# MCU.net
KiCad netlist of a schematic drawn in Altium Designer
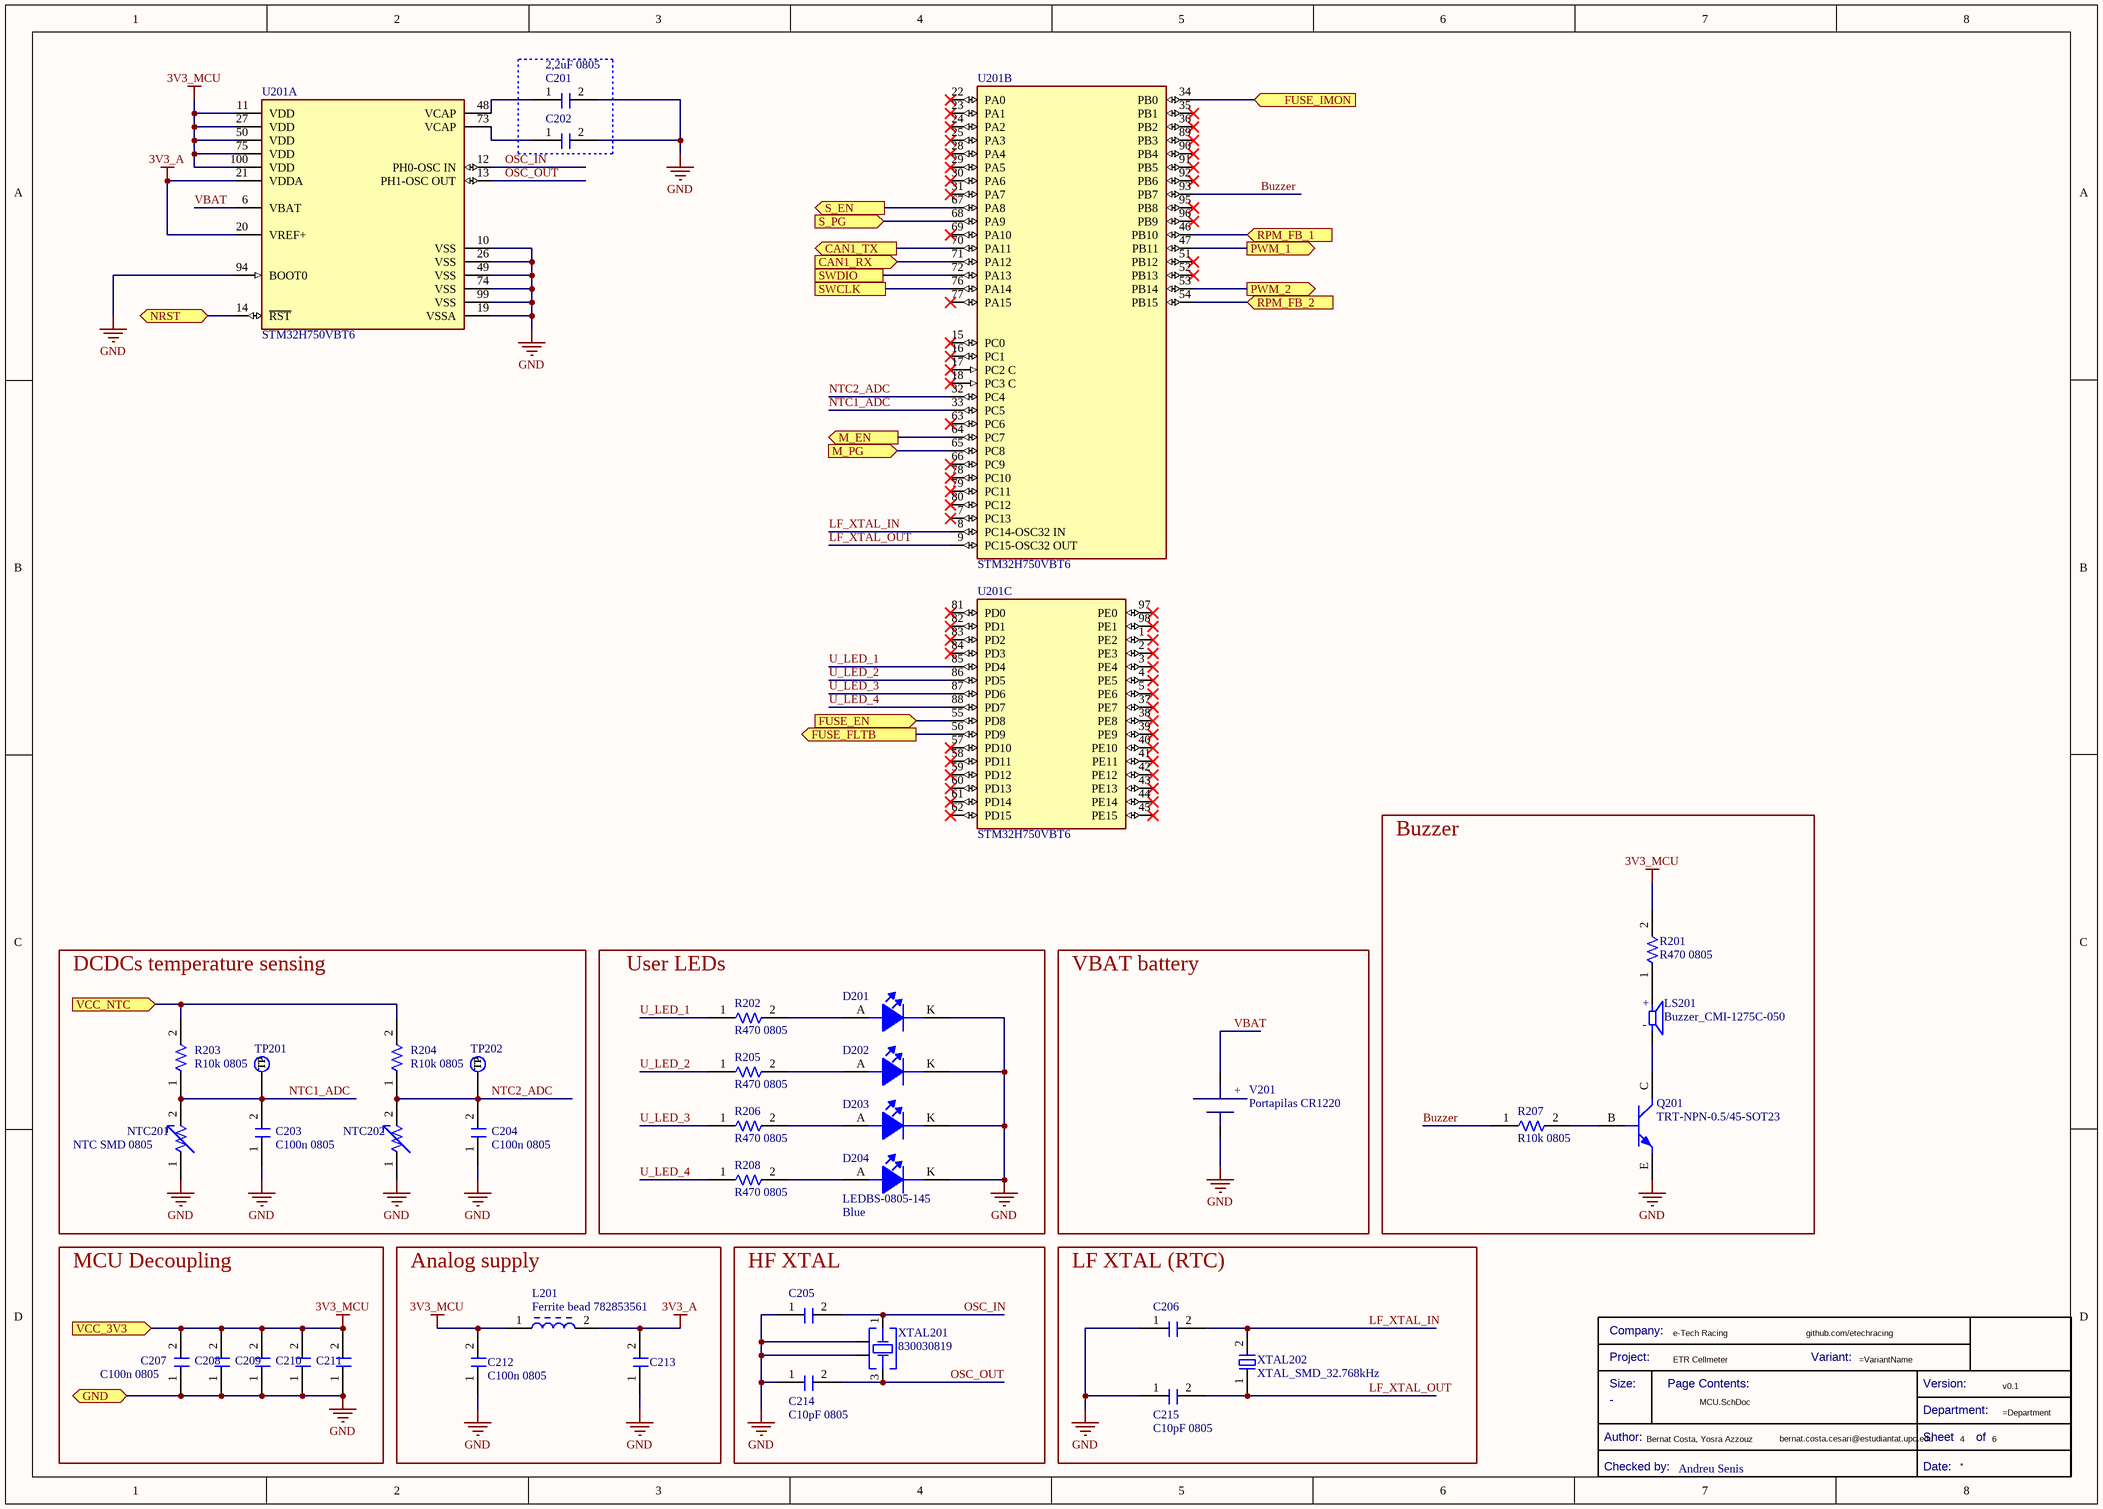
[diagram p0: MCU.SchDoc]

(export (version "E")
  (design (tool "Eeschema 10.0.6"))
  (components
    (comp (ref "C201")
      (value "2,2uF 0805")
      (footprint "C0805FNPC-W")
      (fields
        (field (name "MANUFACTURER") "Wurth Electronics")
        (field (name "TOLERANCE") "20%")
        (field (name "MANUFACTURER PART NUMBER") "885012107011")
        (field (name ".CREATOR") "DR")
      )
      (libsource (lib "EMEA- E-Tech Racing- I'Escola d'Enginyeria de Barcelona Est") (part "C100p-50V-0805FNPC-C0G/NP0"))
    )
    (comp (ref "C202")
      (value "2,2uF 0805")
      (footprint "C0805FNPC-W")
      (fields
        (field (name "MANUFACTURER") "Wurth Electronics")
        (field (name "TOLERANCE") "20%")
        (field (name "MANUFACTURER PART NUMBER") "885012107011")
        (field (name ".CREATOR") "DR")
      )
      (libsource (lib "EMEA- E-Tech Racing- I'Escola d'Enginyeria de Barcelona Est") (part "C100p-50V-0805FNPC-C0G/NP0"))
    )
    (comp (ref "C203")
      (value "C100n 0805")
      (footprint "C0805FNPC-R")
      (description "Cap, 0.1ΜF, 50V, 10%, X7R, 0805")
      (fields (field (name "TOLERANCE") "10%") (field (name ".CREATOR") "DR"))
      (libsource (lib "EMEA- E-Tech Racing- I'Escola d'Enginyeria de Barcelona Est") (part "C100p-50V-0805FNPC-C0G/NP0"))
    )
    (comp (ref "C204")
      (value "C100n 0805")
      (footprint "C0805FNPC-R")
      (description "Cap, 0.1ΜF, 50V, 10%, X7R, 0805")
      (fields (field (name "TOLERANCE") "10%") (field (name ".CREATOR") "DR"))
      (libsource (lib "EMEA- E-Tech Racing- I'Escola d'Enginyeria de Barcelona Est") (part "C100p-50V-0805FNPC-C0G/NP0"))
    )
    (comp (ref "C205")
      (value "C10pF_0805_50V")
      (footprint "WCAP-CSGP_0805_L2W1.25H0.6_Reflow")
      (libsource (lib "EMEA- E-Tech Racing- I'Escola d'Enginyeria de Barcelona Est") (part "C100p-50V-0805FNPC-C0G/NP0"))
    )
    (comp (ref "C206")
      (value "C10pF_0805_50V")
      (footprint "WCAP-CSGP_0805_L2W1.25H0.6_Reflow")
      (libsource (lib "EMEA- E-Tech Racing- I'Escola d'Enginyeria de Barcelona Est") (part "C100p-50V-0805FNPC-C0G/NP0"))
    )
    (comp (ref "C207")
      (value "C100n-50V-0805FNPC-X7R")
      (footprint "C0805FNPC-R")
      (description "Cap, 0.1ΜF, 50V, 10%, X7R, 0805")
      (fields (field (name "TOLERANCE") "10%") (field (name ".CREATOR") "DR"))
      (libsource (lib "EMEA- E-Tech Racing- I'Escola d'Enginyeria de Barcelona Est") (part "C100p-50V-0805FNPC-C0G/NP0"))
    )
    (comp (ref "C208")
      (value "C100n-50V-0805FNPC-X7R")
      (footprint "C0805FNPC-R")
      (description "Cap, 0.1ΜF, 50V, 10%, X7R, 0805")
      (fields (field (name "TOLERANCE") "10%") (field (name ".CREATOR") "DR"))
      (libsource (lib "EMEA- E-Tech Racing- I'Escola d'Enginyeria de Barcelona Est") (part "C100p-50V-0805FNPC-C0G/NP0"))
    )
    (comp (ref "C209")
      (value "C100n-50V-0805FNPC-X7R")
      (footprint "C0805FNPC-R")
      (description "Cap, 0.1ΜF, 50V, 10%, X7R, 0805")
      (fields (field (name "TOLERANCE") "10%") (field (name ".CREATOR") "DR"))
      (libsource (lib "EMEA- E-Tech Racing- I'Escola d'Enginyeria de Barcelona Est") (part "C100p-50V-0805FNPC-C0G/NP0"))
    )
    (comp (ref "C210")
      (value "C100n-50V-0805FNPC-X7R")
      (footprint "C0805FNPC-R")
      (description "Cap, 0.1ΜF, 50V, 10%, X7R, 0805")
      (fields (field (name "TOLERANCE") "10%") (field (name ".CREATOR") "DR"))
      (libsource (lib "EMEA- E-Tech Racing- I'Escola d'Enginyeria de Barcelona Est") (part "C100p-50V-0805FNPC-C0G/NP0"))
    )
    (comp (ref "C211")
      (value "C100n 0805")
      (footprint "C0805FNPC-R")
      (description "Cap, 0.1ΜF, 50V, 10%, X7R, 0805")
      (fields (field (name "TOLERANCE") "10%") (field (name ".CREATOR") "DR"))
      (libsource (lib "EMEA- E-Tech Racing- I'Escola d'Enginyeria de Barcelona Est") (part "C100p-50V-0805FNPC-C0G/NP0"))
    )
    (comp (ref "C212")
      (value "C100n 0805")
      (footprint "C0805FNPC-R")
      (description "Cap, 0.1ΜF, 50V, 10%, X7R, 0805")
      (fields (field (name "TOLERANCE") "10%") (field (name ".CREATOR") "DR"))
      (libsource (lib "EMEA- E-Tech Racing- I'Escola d'Enginyeria de Barcelona Est") (part "C100p-50V-0805FNPC-C0G/NP0"))
    )
    (comp (ref "C213")
      (value "C100n-50V-0805FNPC-X7R")
      (footprint "C0805FNPC-R")
      (description "Cap, 0.1ΜF, 50V, 10%, X7R, 0805")
      (fields (field (name "TOLERANCE") "10%") (field (name ".CREATOR") "DR"))
      (libsource (lib "EMEA- E-Tech Racing- I'Escola d'Enginyeria de Barcelona Est") (part "C100p-50V-0805FNPC-C0G/NP0"))
    )
    (comp (ref "C214")
      (value "C10pF 0805")
      (footprint "WCAP-CSGP_0805_L2W1.25H0.6_Reflow")
      (libsource (lib "EMEA- E-Tech Racing- I'Escola d'Enginyeria de Barcelona Est") (part "C100p-50V-0805FNPC-C0G/NP0"))
    )
    (comp (ref "C215")
      (value "C10pF 0805")
      (footprint "WCAP-CSGP_0805_L2W1.25H0.6_Reflow")
      (libsource (lib "EMEA- E-Tech Racing- I'Escola d'Enginyeria de Barcelona Est") (part "C100p-50V-0805FNPC-C0G/NP0"))
    )
    (comp (ref "D201")
      (value "LEDBS-0805-145")
      (footprint "LED_0805_WE")
      (description "LED BLUE CLEAR 0805 SMD")
      (fields (field (name ".CREATOR") "GP"))
      (libsource (lib "EMEA- E-Tech Racing- I'Escola d'Enginyeria de Barcelona Est") (part "LEDBS-1206-145"))
    )
    (comp (ref "D202")
      (value "LEDBS-0805-145")
      (footprint "LED_0805_WE")
      (description "LED BLUE CLEAR 0805 SMD")
      (fields (field (name ".CREATOR") "GP"))
      (libsource (lib "EMEA- E-Tech Racing- I'Escola d'Enginyeria de Barcelona Est") (part "LEDBS-1206-145"))
    )
    (comp (ref "D203")
      (value "LEDBS-0805-145")
      (footprint "LED_0805_WE")
      (description "LED BLUE CLEAR 0805 SMD")
      (fields (field (name ".CREATOR") "GP"))
      (libsource (lib "EMEA- E-Tech Racing- I'Escola d'Enginyeria de Barcelona Est") (part "LEDBS-1206-145"))
    )
    (comp (ref "D204")
      (value "LEDBS-0805-145")
      (footprint "LED_0805_WE")
      (description "LED BLUE CLEAR 0805 SMD")
      (fields (field (name "COLOR") "Blue") (field (name ".CREATOR") "GP"))
      (libsource (lib "EMEA- E-Tech Racing- I'Escola d'Enginyeria de Barcelona Est") (part "LEDBS-1206-145"))
    )
    (comp (ref "L201")
      (value "Ferrite bead 782853561")
      (footprint "L_Ferrite_bead_0805")
      (fields
        (field (name "TOLERANCE") "25%")
        (field (name "MANUFACTURER PART NUMBER") "BLM18EG331TN1D")
        (field (name "MANUFACTURER") "Murata")
        (field (name ".CREATOR") "GP")
      )
      (libsource (lib "EMEA- E-Tech Racing- I'Escola d'Enginyeria de Barcelona Est") (part "L_Ferrite_bead_782853561"))
    )
    (comp (ref "LS201")
      (value "Buzzer_CMI-1275C-050")
      (footprint "CUI_CMI-1275C-050")
      (description "12 mm, 5 Vdc, 90 dB, 3.1 kHz, Through Hole, Magnetic Audio Indicator Buzzer")
      (fields
        (field (name "MF") "CUI Devices")
        (field (name "MP") "CMI-1275C-050")
        (field (name "SOURCE") "CommonFiles_Library.SchLib")
      )
      (libsource (lib "EMEA- E-Tech Racing- I'Escola d'Enginyeria de Barcelona Est") (part "Buzzer_CMI-1275C-050"))
    )
    (comp (ref "NTC201")
      (value "NTC SMD 0805")
      (footprint "RESC2012X10N")
      (description "NTC 0805 package 10kR")
      (libsource (lib "EMEA- E-Tech Racing- I'Escola d'Enginyeria de Barcelona Est") (part "0805"))
    )
    (comp (ref "NTC202")
      (value "NTC SMD 0805")
      (footprint "RESC2012X10N")
      (description "NTC 0805 package 10kR")
      (libsource (lib "EMEA- E-Tech Racing- I'Escola d'Enginyeria de Barcelona Est") (part "0805"))
    )
    (comp (ref "Q201")
      (value "TRT-NPN-0.5/45-SOT23")
      (footprint "TRT-NPN-0.5/45-SOT23")
      (description "ON Semi BC817-25LT1G NPN Bipolar Transistor; 0.5 A; 45 V; 3-Pin SOT-23")
      (fields (field (name ".CREATOR") "GP"))
      (libsource (lib "EMEA- E-Tech Racing- I'Escola d'Enginyeria de Barcelona Est") (part "TRT-NPN-0.5/45-SOT23"))
    )
    (comp (ref "R201")
      (value "R470 0805")
      (footprint "R0805FTK")
      (description "Res Thick Film 0805 470 Ohm 1% 1/8W ±100ppm/°C Molded SMD SMD Paper Tape on Plastic Reel")
      (fields (field (name "TOLERANCE") "1%") (field (name ".CREATOR") "DR"))
      (libsource (lib "EMEA- E-Tech Racing- I'Escola d'Enginyeria de Barcelona Est") (part "R9.09K-1206FTK"))
    )
    (comp (ref "R202")
      (value "R470 0805")
      (footprint "R0805FTK")
      (description "Res Thick Film 0805 470 Ohm 1% 1/8W ±100ppm/°C Molded SMD SMD Paper Tape on Plastic Reel")
      (fields (field (name "TOLERANCE") "1%") (field (name ".CREATOR") "DR"))
      (libsource (lib "EMEA- E-Tech Racing- I'Escola d'Enginyeria de Barcelona Est") (part "R9.09K-1206FTK"))
    )
    (comp (ref "R203")
      (value "R10k 0805")
      (footprint "R0805FTK")
      (fields (field (name "TOLERANCE") "5%") (field (name ".CREATOR") "DR"))
      (libsource (lib "EMEA- E-Tech Racing- I'Escola d'Enginyeria de Barcelona Est") (part "R9.09K-1206FTK"))
    )
    (comp (ref "R204")
      (value "R10k 0805")
      (footprint "R0805FTK")
      (fields (field (name "TOLERANCE") "5%") (field (name ".CREATOR") "DR"))
      (libsource (lib "EMEA- E-Tech Racing- I'Escola d'Enginyeria de Barcelona Est") (part "R9.09K-1206FTK"))
    )
    (comp (ref "R205")
      (value "R470 0805")
      (footprint "R0805FTK")
      (description "Res Thick Film 0805 470 Ohm 1% 1/8W ±100ppm/°C Molded SMD SMD Paper Tape on Plastic Reel")
      (fields (field (name "TOLERANCE") "1%") (field (name ".CREATOR") "DR"))
      (libsource (lib "EMEA- E-Tech Racing- I'Escola d'Enginyeria de Barcelona Est") (part "R9.09K-1206FTK"))
    )
    (comp (ref "R206")
      (value "R470 0805")
      (footprint "R0805FTK")
      (description "Res Thick Film 0805 470 Ohm 1% 1/8W ±100ppm/°C Molded SMD SMD Paper Tape on Plastic Reel")
      (fields (field (name "TOLERANCE") "1%") (field (name ".CREATOR") "DR"))
      (libsource (lib "EMEA- E-Tech Racing- I'Escola d'Enginyeria de Barcelona Est") (part "R9.09K-1206FTK"))
    )
    (comp (ref "R207")
      (value "R10k 0805")
      (footprint "R0805FTK")
      (fields (field (name "TOLERANCE") "5%") (field (name ".CREATOR") "DR"))
      (libsource (lib "EMEA- E-Tech Racing- I'Escola d'Enginyeria de Barcelona Est") (part "R9.09K-1206FTK"))
    )
    (comp (ref "R208")
      (value "R470 0805")
      (footprint "R0805FTK")
      (description "Res Thick Film 0805 470 Ohm 1% 1/8W ±100ppm/°C Molded SMD SMD Paper Tape on Plastic Reel")
      (fields (field (name "TOLERANCE") "1%") (field (name ".CREATOR") "DR"))
      (libsource (lib "EMEA- E-Tech Racing- I'Escola d'Enginyeria de Barcelona Est") (part "R9.09K-1206FTK"))
    )
    (comp (ref "TP201")
      (value "TestPoint")
      (footprint "TestPoint")
      (description "Test Point 1x1 mm")
      (fields (field (name ".SCHCHECK") "GP") (field (name ".CREATOR") "GP") (field (name ".PCBCHECK") "GP"))
      (libsource (lib "EMEA- E-Tech Racing- I'Escola d'Enginyeria de Barcelona Est") (part "TestPoint"))
    )
    (comp (ref "TP202")
      (value "TestPoint")
      (footprint "TestPoint")
      (description "Test Point 1x1 mm")
      (fields (field (name ".SCHCHECK") "GP") (field (name ".CREATOR") "GP") (field (name ".PCBCHECK") "GP"))
      (libsource (lib "EMEA- E-Tech Racing- I'Escola d'Enginyeria de Barcelona Est") (part "TestPoint"))
    )
    (comp (ref "U201")
      (value "STM32H750VBT6")
      (footprint "FP-LQFP100-1L-IPC_A")
      (description "RISC Microcontroller, 32-Bit, FLASH, 400MHz, CMOS, PQFP100")
      (libsource (lib "EMEA- E-Tech Racing- I'Escola d'Enginyeria de Barcelona Est") (part "aca449acb2b80670ba40d015d68dc7a"))
    )
    (comp (ref "V201")
      (value "Portapilas CR1220")
      (footprint "Portapilas CR1220-Footprint-1")
      (description "237-8301 Portapilas para 1 pila CR1220, montaje Montaje superficial")
      (libsource (lib "EMEA- E-Tech Racing- I'Escola d'Enginyeria de Barcelona Est") (part "Portapilas CR1220"))
    )
    (comp (ref "XTAL201")
      (value "830030819")
      (footprint "WE-XTAL_CFPX-104")
      (description "WE-XTAL Quartz Crystal, SMT, CFPX-104, 16MHz, +/-50ppm")
      (fields (field (name "MANUFACTURER") "Wurth Elektronik"))
      (libsource (lib "EMEA- E-Tech Racing- I'Escola d'Enginyeria de Barcelona Est") (part "830030819"))
    )
    (comp (ref "XTAL202")
      (value "XTAL_SMD_32.768kHz")
      (footprint "XTAL_ABS06-32.768KHZ-9-T")
      (fields (field (name "SOURCE") "CommonFiles_Library.SchLib"))
      (libsource (lib "EMEA- E-Tech Racing- I'Escola d'Enginyeria de Barcelona Est") (part "XTAL_SMD_32.768kHz"))
    )
  )
  (nets
    (net (code "1") (name "/Buzzer") (class "Default")
      (node (ref "R207") (pin "1") (pinfunction "1_1") (pintype "passive"))
      (node (ref "U201") (pin "93") (pinfunction "PB7_93") (pintype "bidirectional"))
    )
    (net (code "2") (name "/CAN1_RX") (class "Default")
      (node (ref "U201") (pin "71") (pinfunction "PA12_71") (pintype "bidirectional"))
    )
    (net (code "3") (name "/CAN1_TX") (class "Default")
      (node (ref "U201") (pin "70") (pinfunction "PA11_70") (pintype "bidirectional"))
    )
    (net (code "4") (name "/FUSE_EN") (class "Default")
      (node (ref "U201") (pin "55") (pinfunction "PD8_55") (pintype "bidirectional"))
    )
    (net (code "5") (name "/FUSE_FLTB") (class "Default")
      (node (ref "U201") (pin "56") (pinfunction "PD9_56") (pintype "bidirectional"))
    )
    (net (code "6") (name "/FUSE_IMON") (class "Default")
      (node (ref "U201") (pin "34") (pinfunction "PB0_34") (pintype "bidirectional"))
    )
    (net (code "7") (name "/LF_XTAL_IN") (class "Default")
      (node (ref "C206") (pin "2") (pinfunction "2_2") (pintype "passive"))
      (node (ref "U201") (pin "8") (pinfunction "PC14-OSC32_IN_8") (pintype "bidirectional"))
      (node (ref "XTAL202") (pin "2") (pinfunction "2_2") (pintype "passive"))
    )
    (net (code "8") (name "/LF_XTAL_OUT") (class "Default")
      (node (ref "C215") (pin "2") (pinfunction "2_2") (pintype "passive"))
      (node (ref "U201") (pin "9") (pinfunction "PC15-OSC32_OUT_9") (pintype "bidirectional"))
      (node (ref "XTAL202") (pin "1") (pinfunction "1_1") (pintype "passive"))
    )
    (net (code "9") (name "/M_EN") (class "Default")
      (node (ref "U201") (pin "64") (pinfunction "PC7_64") (pintype "bidirectional"))
    )
    (net (code "10") (name "/M_PG") (class "Default")
      (node (ref "U201") (pin "65") (pinfunction "PC8_65") (pintype "bidirectional"))
    )
    (net (code "11") (name "/NRST") (class "Default")
      (node (ref "U201") (pin "14") (pinfunction "~{RST}_14") (pintype "bidirectional"))
    )
    (net (code "12") (name "/NTC1_ADC") (class "Default")
      (node (ref "C203") (pin "2") (pinfunction "2_2") (pintype "passive"))
      (node (ref "NTC201") (pin "2") (pinfunction "2_2") (pintype "passive"))
      (node (ref "R203") (pin "1") (pinfunction "1_1") (pintype "passive"))
      (node (ref "TP201") (pin "1") (pinfunction "TP_1") (pintype "passive"))
      (node (ref "U201") (pin "33") (pinfunction "PC5_33") (pintype "bidirectional"))
    )
    (net (code "13") (name "/NTC2_ADC") (class "Default")
      (node (ref "C204") (pin "2") (pinfunction "2_2") (pintype "passive"))
      (node (ref "NTC202") (pin "2") (pinfunction "2_2") (pintype "passive"))
      (node (ref "R204") (pin "1") (pinfunction "1_1") (pintype "passive"))
      (node (ref "TP202") (pin "1") (pinfunction "TP_1") (pintype "passive"))
      (node (ref "U201") (pin "32") (pinfunction "PC4_32") (pintype "bidirectional"))
    )
    (net (code "14") (name "/OSC_IN") (class "Default")
      (node (ref "C205") (pin "2") (pinfunction "2_2") (pintype "passive"))
      (node (ref "U201") (pin "12") (pinfunction "PH0-OSC_IN_12") (pintype "bidirectional"))
      (node (ref "XTAL201") (pin "1") (pinfunction "Crystal_1") (pintype "passive"))
    )
    (net (code "15") (name "/OSC_OUT") (class "Default")
      (node (ref "C214") (pin "2") (pinfunction "2_2") (pintype "passive"))
      (node (ref "U201") (pin "13") (pinfunction "PH1-OSC_OUT_13") (pintype "bidirectional"))
      (node (ref "XTAL201") (pin "3") (pinfunction "Crystal_3") (pintype "passive"))
    )
    (net (code "16") (name "/PWM_1") (class "Default")
      (node (ref "U201") (pin "47") (pinfunction "PB11_47") (pintype "bidirectional"))
    )
    (net (code "17") (name "/PWM_2") (class "Default")
      (node (ref "U201") (pin "53") (pinfunction "PB14_53") (pintype "bidirectional"))
    )
    (net (code "18") (name "/RPM_FB_1") (class "Default")
      (node (ref "U201") (pin "46") (pinfunction "PB10_46") (pintype "bidirectional"))
    )
    (net (code "19") (name "/RPM_FB_2") (class "Default")
      (node (ref "U201") (pin "54") (pinfunction "PB15_54") (pintype "bidirectional"))
    )
    (net (code "20") (name "/SWCLK") (class "Default")
      (node (ref "U201") (pin "76") (pinfunction "PA14_76") (pintype "bidirectional"))
    )
    (net (code "21") (name "/SWDIO") (class "Default")
      (node (ref "U201") (pin "72") (pinfunction "PA13_72") (pintype "bidirectional"))
    )
    (net (code "22") (name "/S_EN") (class "Default")
      (node (ref "U201") (pin "67") (pinfunction "PA8_67") (pintype "bidirectional"))
    )
    (net (code "23") (name "/S_PG") (class "Default")
      (node (ref "U201") (pin "68") (pinfunction "PA9_68") (pintype "bidirectional"))
    )
    (net (code "24") (name "/U_LED_1") (class "Default")
      (node (ref "R202") (pin "1") (pinfunction "1_1") (pintype "passive"))
      (node (ref "U201") (pin "85") (pinfunction "PD4_85") (pintype "bidirectional"))
    )
    (net (code "25") (name "/U_LED_2") (class "Default")
      (node (ref "R205") (pin "1") (pinfunction "1_1") (pintype "passive"))
      (node (ref "U201") (pin "86") (pinfunction "PD5_86") (pintype "bidirectional"))
    )
    (net (code "26") (name "/U_LED_3") (class "Default")
      (node (ref "R206") (pin "1") (pinfunction "1_1") (pintype "passive"))
      (node (ref "U201") (pin "87") (pinfunction "PD6_87") (pintype "bidirectional"))
    )
    (net (code "27") (name "/U_LED_4") (class "Default")
      (node (ref "R208") (pin "1") (pinfunction "1_1") (pintype "passive"))
      (node (ref "U201") (pin "88") (pinfunction "PD7_88") (pintype "bidirectional"))
    )
    (net (code "28") (name "/VBAT") (class "Default")
      (node (ref "U201") (pin "6") (pinfunction "VBAT_6") (pintype "power_in"))
      (node (ref "V201") (pin "1") (pinfunction "V+_1") (pintype "passive"))
    )
    (net (code "29") (name "/VCC_NTC") (class "Default")
      (node (ref "R203") (pin "2") (pinfunction "2_2") (pintype "passive"))
      (node (ref "R204") (pin "2") (pinfunction "2_2") (pintype "passive"))
    )
    (net (code "30") (name "3V3_A") (class "Default")
      (node (ref "C213") (pin "2") (pinfunction "2_2") (pintype "passive"))
      (node (ref "L201") (pin "2") (pinfunction "2_2") (pintype "passive"))
      (node (ref "U201") (pin "20") (pinfunction "VREF+_20") (pintype "power_in"))
      (node (ref "U201") (pin "21") (pinfunction "VDDA_21") (pintype "power_in"))
    )
    (net (code "31") (name "3V3_MCU") (class "Default")
      (node (ref "C207") (pin "2") (pinfunction "2_2") (pintype "passive"))
      (node (ref "C208") (pin "2") (pinfunction "2_2") (pintype "passive"))
      (node (ref "C209") (pin "2") (pinfunction "2_2") (pintype "passive"))
      (node (ref "C210") (pin "2") (pinfunction "2_2") (pintype "passive"))
      (node (ref "C211") (pin "2") (pinfunction "2_2") (pintype "passive"))
      (node (ref "C212") (pin "2") (pinfunction "2_2") (pintype "passive"))
      (node (ref "L201") (pin "1") (pinfunction "1_1") (pintype "passive"))
      (node (ref "R201") (pin "2") (pinfunction "2_2") (pintype "passive"))
      (node (ref "U201") (pin "100") (pinfunction "VDD_100") (pintype "power_in"))
      (node (ref "U201") (pin "11") (pinfunction "VDD_11") (pintype "power_in"))
      (node (ref "U201") (pin "27") (pinfunction "VDD_27") (pintype "power_in"))
      (node (ref "U201") (pin "50") (pinfunction "VDD_50") (pintype "power_in"))
      (node (ref "U201") (pin "75") (pinfunction "VDD_75") (pintype "power_in"))
    )
    (net (code "32") (name "GND") (class "Default")
      (node (ref "C201") (pin "2") (pinfunction "2_2") (pintype "passive"))
      (node (ref "C202") (pin "2") (pinfunction "2_2") (pintype "passive"))
      (node (ref "C203") (pin "1") (pinfunction "1_1") (pintype "passive"))
      (node (ref "C204") (pin "1") (pinfunction "1_1") (pintype "passive"))
      (node (ref "C205") (pin "1") (pinfunction "1_1") (pintype "passive"))
      (node (ref "C206") (pin "1") (pinfunction "1_1") (pintype "passive"))
      (node (ref "C207") (pin "1") (pinfunction "1_1") (pintype "passive"))
      (node (ref "C208") (pin "1") (pinfunction "1_1") (pintype "passive"))
      (node (ref "C209") (pin "1") (pinfunction "1_1") (pintype "passive"))
      (node (ref "C210") (pin "1") (pinfunction "1_1") (pintype "passive"))
      (node (ref "C211") (pin "1") (pinfunction "1_1") (pintype "passive"))
      (node (ref "C212") (pin "1") (pinfunction "1_1") (pintype "passive"))
      (node (ref "C213") (pin "1") (pinfunction "1_1") (pintype "passive"))
      (node (ref "C214") (pin "1") (pinfunction "1_1") (pintype "passive"))
      (node (ref "C215") (pin "1") (pinfunction "1_1") (pintype "passive"))
      (node (ref "D201") (pin "K") (pinfunction "K_K") (pintype "passive"))
      (node (ref "D202") (pin "K") (pinfunction "K_K") (pintype "passive"))
      (node (ref "D203") (pin "K") (pinfunction "K_K") (pintype "passive"))
      (node (ref "D204") (pin "K") (pinfunction "K_K") (pintype "passive"))
      (node (ref "NTC201") (pin "1") (pinfunction "1_1") (pintype "passive"))
      (node (ref "NTC202") (pin "1") (pinfunction "1_1") (pintype "passive"))
      (node (ref "Q201") (pin "E") (pinfunction "E_E") (pintype "passive"))
      (node (ref "U201") (pin "10") (pinfunction "VSS_10") (pintype "power_in"))
      (node (ref "U201") (pin "19") (pinfunction "VSSA_19") (pintype "power_in"))
      (node (ref "U201") (pin "26") (pinfunction "VSS_26") (pintype "power_in"))
      (node (ref "U201") (pin "49") (pinfunction "VSS_49") (pintype "power_in"))
      (node (ref "U201") (pin "74") (pinfunction "VSS_74") (pintype "power_in"))
      (node (ref "U201") (pin "94") (pinfunction "BOOT0_94") (pintype "input"))
      (node (ref "U201") (pin "99") (pinfunction "VSS_99") (pintype "power_in"))
      (node (ref "V201") (pin "2") (pinfunction "GND_2") (pintype "passive"))
      (node (ref "XTAL201") (pin "2") (pinfunction "GND_&_Lid_2") (pintype "passive"))
      (node (ref "XTAL201") (pin "4") (pinfunction "GND_&_Lid_4") (pintype "passive"))
    )
    (net (code "33") (name "Net-(C201-Pad1)") (class "Default")
      (node (ref "C201") (pin "1") (pinfunction "1_1") (pintype "passive"))
      (node (ref "U201") (pin "48") (pinfunction "VCAP_48") (pintype "power_in"))
    )
    (net (code "34") (name "Net-(C202-Pad1)") (class "Default")
      (node (ref "C202") (pin "1") (pinfunction "1_1") (pintype "passive"))
      (node (ref "U201") (pin "73") (pinfunction "VCAP_73") (pintype "power_in"))
    )
    (net (code "35") (name "Net-(D201-PadA)") (class "Default")
      (node (ref "D201") (pin "A") (pinfunction "A_A") (pintype "passive"))
      (node (ref "R202") (pin "2") (pinfunction "2_2") (pintype "passive"))
    )
    (net (code "36") (name "Net-(D202-PadA)") (class "Default")
      (node (ref "D202") (pin "A") (pinfunction "A_A") (pintype "passive"))
      (node (ref "R205") (pin "2") (pinfunction "2_2") (pintype "passive"))
    )
    (net (code "37") (name "Net-(D203-PadA)") (class "Default")
      (node (ref "D203") (pin "A") (pinfunction "A_A") (pintype "passive"))
      (node (ref "R206") (pin "2") (pinfunction "2_2") (pintype "passive"))
    )
    (net (code "38") (name "Net-(D204-PadA)") (class "Default")
      (node (ref "D204") (pin "A") (pinfunction "A_A") (pintype "passive"))
      (node (ref "R208") (pin "2") (pinfunction "2_2") (pintype "passive"))
    )
    (net (code "39") (name "Net-(LS201-PadN)") (class "Default")
      (node (ref "LS201") (pin "N") (pinfunction "N_N") (pintype "passive"))
      (node (ref "Q201") (pin "C") (pinfunction "C_C") (pintype "passive"))
    )
    (net (code "40") (name "Net-(LS201-PadP)") (class "Default")
      (node (ref "LS201") (pin "P") (pinfunction "P_P") (pintype "passive"))
      (node (ref "R201") (pin "1") (pinfunction "1_1") (pintype "passive"))
    )
    (net (code "41") (name "Net-(Q201-PadB)") (class "Default")
      (node (ref "Q201") (pin "B") (pinfunction "B_B") (pintype "passive"))
      (node (ref "R207") (pin "2") (pinfunction "2_2") (pintype "passive"))
    )
    (net (code "42") (name "unconnected-(U201B-PA0-Pad22)") (class "Default")
      (node (ref "U201") (pin "22") (pinfunction "PA0_22") (pintype "bidirectional+no_connect"))
    )
    (net (code "43") (name "unconnected-(U201B-PA1-Pad23)") (class "Default")
      (node (ref "U201") (pin "23") (pinfunction "PA1_23") (pintype "bidirectional+no_connect"))
    )
    (net (code "44") (name "unconnected-(U201B-PA2-Pad24)") (class "Default")
      (node (ref "U201") (pin "24") (pinfunction "PA2_24") (pintype "bidirectional+no_connect"))
    )
    (net (code "45") (name "unconnected-(U201B-PA3-Pad25)") (class "Default")
      (node (ref "U201") (pin "25") (pinfunction "PA3_25") (pintype "bidirectional+no_connect"))
    )
    (net (code "46") (name "unconnected-(U201B-PA4-Pad28)") (class "Default")
      (node (ref "U201") (pin "28") (pinfunction "PA4_28") (pintype "bidirectional+no_connect"))
    )
    (net (code "47") (name "unconnected-(U201B-PA5-Pad29)") (class "Default")
      (node (ref "U201") (pin "29") (pinfunction "PA5_29") (pintype "bidirectional+no_connect"))
    )
    (net (code "48") (name "unconnected-(U201B-PA6-Pad30)") (class "Default")
      (node (ref "U201") (pin "30") (pinfunction "PA6_30") (pintype "bidirectional+no_connect"))
    )
    (net (code "49") (name "unconnected-(U201B-PA7-Pad31)") (class "Default")
      (node (ref "U201") (pin "31") (pinfunction "PA7_31") (pintype "bidirectional+no_connect"))
    )
    (net (code "50") (name "unconnected-(U201B-PA10-Pad69)") (class "Default")
      (node (ref "U201") (pin "69") (pinfunction "PA10_69") (pintype "bidirectional+no_connect"))
    )
    (net (code "51") (name "unconnected-(U201B-PA15-Pad77)") (class "Default")
      (node (ref "U201") (pin "77") (pinfunction "PA15_77") (pintype "bidirectional+no_connect"))
    )
    (net (code "52") (name "unconnected-(U201B-PB1-Pad35)") (class "Default")
      (node (ref "U201") (pin "35") (pinfunction "PB1_35") (pintype "bidirectional+no_connect"))
    )
    (net (code "53") (name "unconnected-(U201B-PB2-Pad36)") (class "Default")
      (node (ref "U201") (pin "36") (pinfunction "PB2_36") (pintype "bidirectional+no_connect"))
    )
    (net (code "54") (name "unconnected-(U201B-PB3-Pad89)") (class "Default")
      (node (ref "U201") (pin "89") (pinfunction "PB3_89") (pintype "bidirectional+no_connect"))
    )
    (net (code "55") (name "unconnected-(U201B-PB4-Pad90)") (class "Default")
      (node (ref "U201") (pin "90") (pinfunction "PB4_90") (pintype "bidirectional+no_connect"))
    )
    (net (code "56") (name "unconnected-(U201B-PB5-Pad91)") (class "Default")
      (node (ref "U201") (pin "91") (pinfunction "PB5_91") (pintype "bidirectional+no_connect"))
    )
    (net (code "57") (name "unconnected-(U201B-PB6-Pad92)") (class "Default")
      (node (ref "U201") (pin "92") (pinfunction "PB6_92") (pintype "bidirectional+no_connect"))
    )
    (net (code "58") (name "unconnected-(U201B-PB8-Pad95)") (class "Default")
      (node (ref "U201") (pin "95") (pinfunction "PB8_95") (pintype "bidirectional+no_connect"))
    )
    (net (code "59") (name "unconnected-(U201B-PB9-Pad96)") (class "Default")
      (node (ref "U201") (pin "96") (pinfunction "PB9_96") (pintype "bidirectional+no_connect"))
    )
    (net (code "60") (name "unconnected-(U201B-PB12-Pad51)") (class "Default")
      (node (ref "U201") (pin "51") (pinfunction "PB12_51") (pintype "bidirectional+no_connect"))
    )
    (net (code "61") (name "unconnected-(U201B-PB13-Pad52)") (class "Default")
      (node (ref "U201") (pin "52") (pinfunction "PB13_52") (pintype "bidirectional+no_connect"))
    )
    (net (code "62") (name "unconnected-(U201B-PC0-Pad15)") (class "Default")
      (node (ref "U201") (pin "15") (pinfunction "PC0_15") (pintype "bidirectional+no_connect"))
    )
    (net (code "63") (name "unconnected-(U201B-PC1-Pad16)") (class "Default")
      (node (ref "U201") (pin "16") (pinfunction "PC1_16") (pintype "bidirectional+no_connect"))
    )
    (net (code "64") (name "unconnected-(U201B-PC2_C-Pad17)") (class "Default")
      (node (ref "U201") (pin "17") (pinfunction "PC2_C_17") (pintype "input+no_connect"))
    )
    (net (code "65") (name "unconnected-(U201B-PC3_C-Pad18)") (class "Default")
      (node (ref "U201") (pin "18") (pinfunction "PC3_C_18") (pintype "input+no_connect"))
    )
    (net (code "66") (name "unconnected-(U201B-PC6-Pad63)") (class "Default")
      (node (ref "U201") (pin "63") (pinfunction "PC6_63") (pintype "bidirectional+no_connect"))
    )
    (net (code "67") (name "unconnected-(U201B-PC9-Pad66)") (class "Default")
      (node (ref "U201") (pin "66") (pinfunction "PC9_66") (pintype "bidirectional+no_connect"))
    )
    (net (code "68") (name "unconnected-(U201B-PC10-Pad78)") (class "Default")
      (node (ref "U201") (pin "78") (pinfunction "PC10_78") (pintype "bidirectional+no_connect"))
    )
    (net (code "69") (name "unconnected-(U201B-PC11-Pad79)") (class "Default")
      (node (ref "U201") (pin "79") (pinfunction "PC11_79") (pintype "bidirectional+no_connect"))
    )
    (net (code "70") (name "unconnected-(U201B-PC12-Pad80)") (class "Default")
      (node (ref "U201") (pin "80") (pinfunction "PC12_80") (pintype "bidirectional+no_connect"))
    )
    (net (code "71") (name "unconnected-(U201B-PC13-Pad7)") (class "Default")
      (node (ref "U201") (pin "7") (pinfunction "PC13_7") (pintype "bidirectional+no_connect"))
    )
    (net (code "72") (name "unconnected-(U201C-PD0-Pad81)") (class "Default")
      (node (ref "U201") (pin "81") (pinfunction "PD0_81") (pintype "bidirectional+no_connect"))
    )
    (net (code "73") (name "unconnected-(U201C-PD1-Pad82)") (class "Default")
      (node (ref "U201") (pin "82") (pinfunction "PD1_82") (pintype "bidirectional+no_connect"))
    )
    (net (code "74") (name "unconnected-(U201C-PD2-Pad83)") (class "Default")
      (node (ref "U201") (pin "83") (pinfunction "PD2_83") (pintype "bidirectional+no_connect"))
    )
    (net (code "75") (name "unconnected-(U201C-PD3-Pad84)") (class "Default")
      (node (ref "U201") (pin "84") (pinfunction "PD3_84") (pintype "bidirectional+no_connect"))
    )
    (net (code "76") (name "unconnected-(U201C-PD10-Pad57)") (class "Default")
      (node (ref "U201") (pin "57") (pinfunction "PD10_57") (pintype "bidirectional+no_connect"))
    )
    (net (code "77") (name "unconnected-(U201C-PD11-Pad58)") (class "Default")
      (node (ref "U201") (pin "58") (pinfunction "PD11_58") (pintype "bidirectional+no_connect"))
    )
    (net (code "78") (name "unconnected-(U201C-PD12-Pad59)") (class "Default")
      (node (ref "U201") (pin "59") (pinfunction "PD12_59") (pintype "bidirectional+no_connect"))
    )
    (net (code "79") (name "unconnected-(U201C-PD13-Pad60)") (class "Default")
      (node (ref "U201") (pin "60") (pinfunction "PD13_60") (pintype "bidirectional+no_connect"))
    )
    (net (code "80") (name "unconnected-(U201C-PD14-Pad61)") (class "Default")
      (node (ref "U201") (pin "61") (pinfunction "PD14_61") (pintype "bidirectional+no_connect"))
    )
    (net (code "81") (name "unconnected-(U201C-PD15-Pad62)") (class "Default")
      (node (ref "U201") (pin "62") (pinfunction "PD15_62") (pintype "bidirectional+no_connect"))
    )
    (net (code "82") (name "unconnected-(U201C-PE0-Pad97)") (class "Default")
      (node (ref "U201") (pin "97") (pinfunction "PE0_97") (pintype "bidirectional+no_connect"))
    )
    (net (code "83") (name "unconnected-(U201C-PE1-Pad98)") (class "Default")
      (node (ref "U201") (pin "98") (pinfunction "PE1_98") (pintype "bidirectional+no_connect"))
    )
    (net (code "84") (name "unconnected-(U201C-PE2-Pad1)") (class "Default")
      (node (ref "U201") (pin "1") (pinfunction "PE2_1") (pintype "bidirectional+no_connect"))
    )
    (net (code "85") (name "unconnected-(U201C-PE3-Pad2)") (class "Default")
      (node (ref "U201") (pin "2") (pinfunction "PE3_2") (pintype "bidirectional+no_connect"))
    )
    (net (code "86") (name "unconnected-(U201C-PE4-Pad3)") (class "Default")
      (node (ref "U201") (pin "3") (pinfunction "PE4_3") (pintype "bidirectional+no_connect"))
    )
    (net (code "87") (name "unconnected-(U201C-PE5-Pad4)") (class "Default")
      (node (ref "U201") (pin "4") (pinfunction "PE5_4") (pintype "bidirectional+no_connect"))
    )
    (net (code "88") (name "unconnected-(U201C-PE6-Pad5)") (class "Default")
      (node (ref "U201") (pin "5") (pinfunction "PE6_5") (pintype "bidirectional+no_connect"))
    )
    (net (code "89") (name "unconnected-(U201C-PE7-Pad37)") (class "Default")
      (node (ref "U201") (pin "37") (pinfunction "PE7_37") (pintype "bidirectional+no_connect"))
    )
    (net (code "90") (name "unconnected-(U201C-PE8-Pad38)") (class "Default")
      (node (ref "U201") (pin "38") (pinfunction "PE8_38") (pintype "bidirectional+no_connect"))
    )
    (net (code "91") (name "unconnected-(U201C-PE9-Pad39)") (class "Default")
      (node (ref "U201") (pin "39") (pinfunction "PE9_39") (pintype "bidirectional+no_connect"))
    )
    (net (code "92") (name "unconnected-(U201C-PE10-Pad40)") (class "Default")
      (node (ref "U201") (pin "40") (pinfunction "PE10_40") (pintype "bidirectional+no_connect"))
    )
    (net (code "93") (name "unconnected-(U201C-PE11-Pad41)") (class "Default")
      (node (ref "U201") (pin "41") (pinfunction "PE11_41") (pintype "bidirectional+no_connect"))
    )
    (net (code "94") (name "unconnected-(U201C-PE12-Pad42)") (class "Default")
      (node (ref "U201") (pin "42") (pinfunction "PE12_42") (pintype "bidirectional+no_connect"))
    )
    (net (code "95") (name "unconnected-(U201C-PE13-Pad43)") (class "Default")
      (node (ref "U201") (pin "43") (pinfunction "PE13_43") (pintype "bidirectional+no_connect"))
    )
    (net (code "96") (name "unconnected-(U201C-PE14-Pad44)") (class "Default")
      (node (ref "U201") (pin "44") (pinfunction "PE14_44") (pintype "bidirectional+no_connect"))
    )
    (net (code "97") (name "unconnected-(U201C-PE15-Pad45)") (class "Default")
      (node (ref "U201") (pin "45") (pinfunction "PE15_45") (pintype "bidirectional+no_connect"))
    )
  )
)
